# STM32WL_ADC.net
KiCad netlist of a schematic drawn in Altium Designer
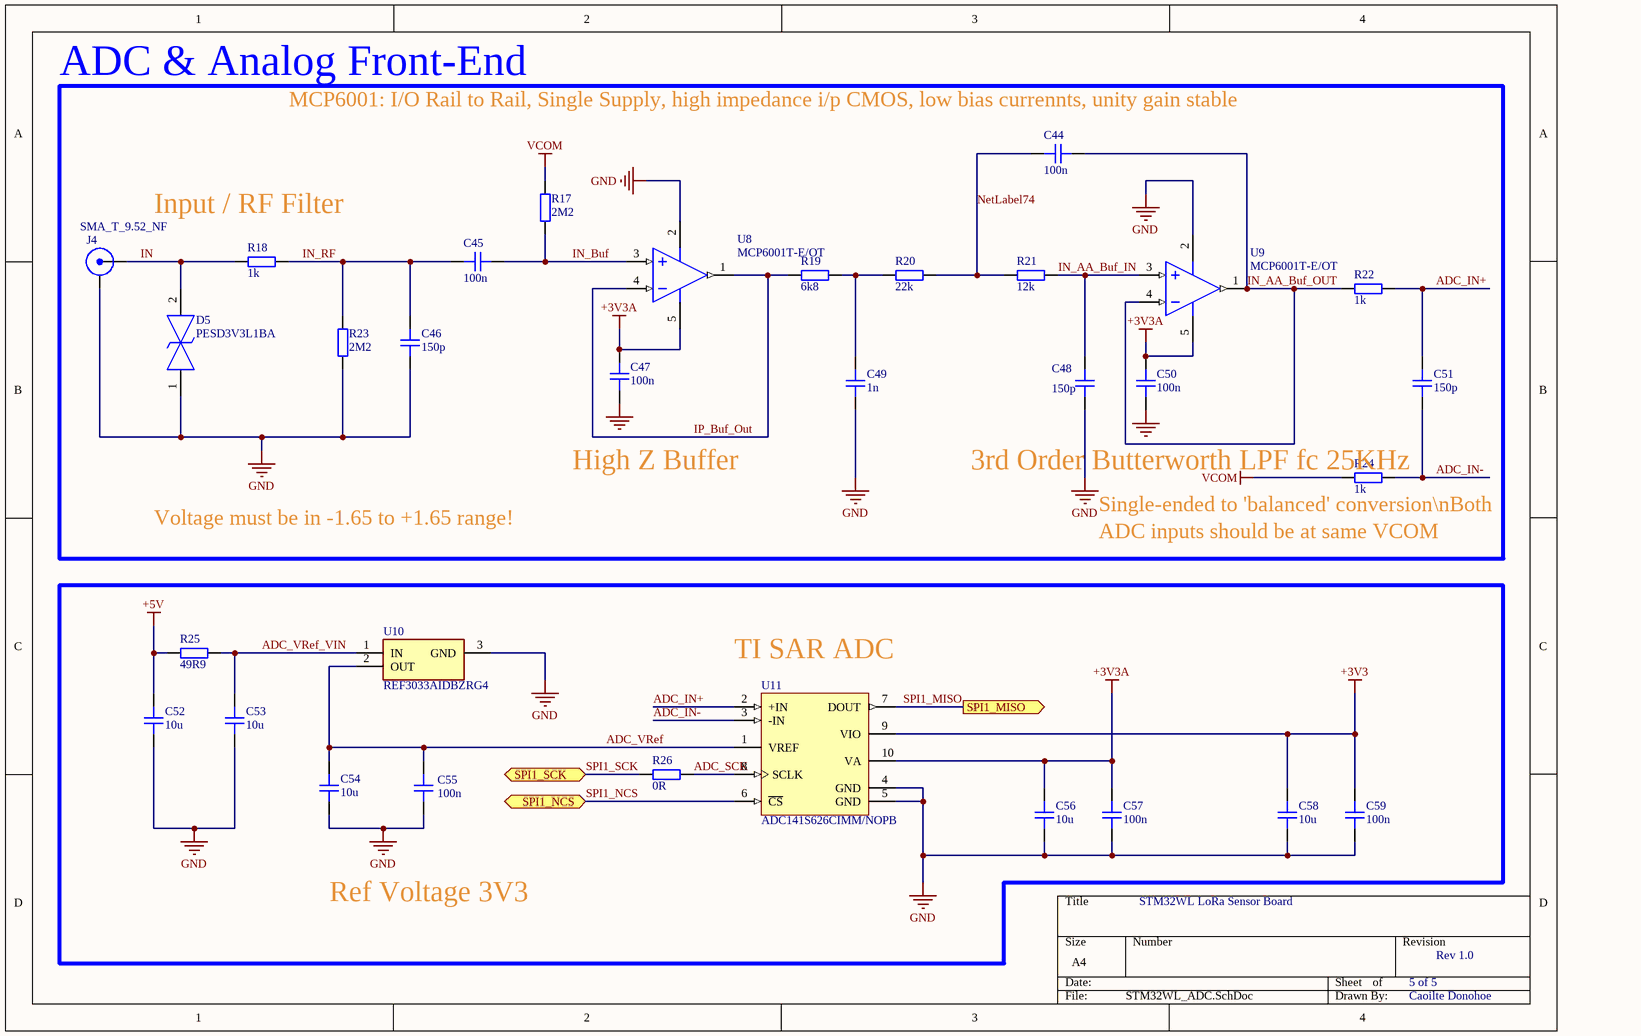
[diagram p0: STM32WL_ADC.SchDoc]

(export (version "E")
  (design (tool "Eeschema 10.0.6"))
  (components
    (comp (ref "C44")
      (value "100n")
      (footprint "CAP_0402")
      (description "Capacitor SMD 0402 16V")
      (libsource (lib "Schematic-Lib-PhilsLab") (part "CAP_0402_16V"))
    )
    (comp (ref "C45")
      (value "100n")
      (footprint "CAP_0402")
      (description "Capacitor SMD 0402 16V")
      (libsource (lib "Schematic-Lib-PhilsLab") (part "CAP_0402_16V"))
    )
    (comp (ref "C46")
      (value "150p")
      (footprint "CAP_0402")
      (description "Capacitor SMD 0402 16V")
      (libsource (lib "Schematic-Lib-PhilsLab") (part "CAP_0402_16V"))
    )
    (comp (ref "C47")
      (value "100n")
      (footprint "CAP_0402")
      (description "Capacitor SMD 0402 16V")
      (libsource (lib "Schematic-Lib-PhilsLab") (part "CAP_0402_16V"))
    )
    (comp (ref "C48")
      (value "150p")
      (footprint "CAP_0402")
      (description "Capacitor SMD 0402 16V")
      (libsource (lib "Schematic-Lib-PhilsLab") (part "CAP_0402_16V"))
    )
    (comp (ref "C49")
      (value "1n")
      (footprint "CAP_0402")
      (description "Capacitor SMD 0402 16V")
      (libsource (lib "Schematic-Lib-PhilsLab") (part "CAP_0402_16V"))
    )
    (comp (ref "C50")
      (value "100n")
      (footprint "CAP_0402")
      (description "Capacitor SMD 0402 16V")
      (libsource (lib "Schematic-Lib-PhilsLab") (part "CAP_0402_16V"))
    )
    (comp (ref "C51")
      (value "150p")
      (footprint "CAP_0402")
      (description "Capacitor SMD 0402 16V")
      (libsource (lib "Schematic-Lib-PhilsLab") (part "CAP_0402_16V"))
    )
    (comp (ref "C52")
      (value "10u")
      (footprint "CAP_0603")
      (description "Capacitor SMD 0603 16V")
      (libsource (lib "Schematic-Lib-PhilsLab") (part "CAP_0603_16V"))
    )
    (comp (ref "C53")
      (value "10u")
      (footprint "CAP_0603")
      (description "Capacitor SMD 0603 16V")
      (libsource (lib "Schematic-Lib-PhilsLab") (part "CAP_0603_16V"))
    )
    (comp (ref "C54")
      (value "10u")
      (footprint "CAP_0603")
      (description "Capacitor SMD 0603 16V")
      (libsource (lib "Schematic-Lib-PhilsLab") (part "CAP_0603_16V"))
    )
    (comp (ref "C55")
      (value "100n")
      (footprint "CAP_0402")
      (description "Capacitor SMD 0402 16V")
      (libsource (lib "Schematic-Lib-PhilsLab") (part "CAP_0402_16V"))
    )
    (comp (ref "C56")
      (value "10u")
      (footprint "CAP_0603")
      (description "Capacitor SMD 0603 16V")
      (libsource (lib "Schematic-Lib-PhilsLab") (part "CAP_0603_16V"))
    )
    (comp (ref "C57")
      (value "100n")
      (footprint "CAP_0402")
      (description "Capacitor SMD 0402 16V")
      (libsource (lib "Schematic-Lib-PhilsLab") (part "CAP_0402_16V"))
    )
    (comp (ref "C58")
      (value "10u")
      (footprint "CAP_0603")
      (description "Capacitor SMD 0603 16V")
      (libsource (lib "Schematic-Lib-PhilsLab") (part "CAP_0603_16V"))
    )
    (comp (ref "C59")
      (value "100n")
      (footprint "CAP_0402")
      (description "Capacitor SMD 0402 16V")
      (libsource (lib "Schematic-Lib-PhilsLab") (part "CAP_0402_16V"))
    )
    (comp (ref "D5")
      (value "PESD3V3L1BA")
      (footprint "SamacSys:SOD2512X110N")
      (description "TVS Diode (Bi-directional)")
      (libsource (lib "*") (part "PESD3V3L1BA"))
    )
    (comp (ref "J4")
      (value "SMA_T_9.52_NF")
      (footprint "CO_SAMTEC_SMA-J-P-ST-EMI")
      (description "SMA End Launch Jack 1.0 mm Board, 50 ohm")
      (fields
        (field (name "MANUFACTURER") "COAX CONNECTORS LTD")
        (field (name "MANUFACTURER_PART_NUMBER") "30-462-D3-1.1mm")
      )
      (libsource (lib "MB1789_HP") (part "SMA_T_9.52_NF"))
    )
    (comp (ref "R17")
      (value "2M2")
      (footprint "RES_0402")
      (description "Resistor SMD 0402")
      (libsource (lib "Schematic-Lib-PhilsLab") (part "RES_0402"))
    )
    (comp (ref "R18")
      (value "1k")
      (footprint "RES_0402")
      (description "Resistor SMD 0402")
      (libsource (lib "Schematic-Lib-PhilsLab") (part "RES_0402"))
    )
    (comp (ref "R19")
      (value "6k8")
      (footprint "RES_0402")
      (description "Resistor SMD 0402")
      (libsource (lib "Schematic-Lib-PhilsLab") (part "RES_0402"))
    )
    (comp (ref "R20")
      (value "22k")
      (footprint "RES_0402")
      (description "Resistor SMD 0402")
      (libsource (lib "Schematic-Lib-PhilsLab") (part "RES_0402"))
    )
    (comp (ref "R21")
      (value "12k")
      (footprint "RES_0402")
      (description "Resistor SMD 0402")
      (libsource (lib "Schematic-Lib-PhilsLab") (part "RES_0402"))
    )
    (comp (ref "R22")
      (value "1k")
      (footprint "RES_0402")
      (description "Resistor SMD 0402")
      (libsource (lib "Schematic-Lib-PhilsLab") (part "RES_0402"))
    )
    (comp (ref "R23")
      (value "2M2")
      (footprint "RES_0402")
      (description "Resistor SMD 0402")
      (libsource (lib "Schematic-Lib-PhilsLab") (part "RES_0402"))
    )
    (comp (ref "R24")
      (value "1k")
      (footprint "RES_0402")
      (description "Resistor SMD 0402")
      (libsource (lib "Schematic-Lib-PhilsLab") (part "RES_0402"))
    )
    (comp (ref "R25")
      (value "49R9")
      (footprint "RES_0402")
      (description "Resistor SMD 0402")
      (libsource (lib "Schematic-Lib-PhilsLab") (part "RES_0402"))
    )
    (comp (ref "R26")
      (value "0R")
      (footprint "RES_0402")
      (description "Resistor SMD 0402")
      (libsource (lib "Schematic-Lib-PhilsLab") (part "RES_0402"))
    )
    (comp (ref "U8")
      (value "MCP6001T-E/OT")
      (footprint "SOT-23-OT5_L")
      (description "None")
      (fields (field (name "VOLTAGE") "6V"))
      (libsource (lib "Altium Content Vault") (part "AMP-OPA-MCP6001-SOT5"))
    )
    (comp (ref "U9")
      (value "MCP6001T-E/OT")
      (footprint "SOT-23-OT5_L")
      (description "None")
      (fields (field (name "VOLTAGE") "6V"))
      (libsource (lib "Altium Content Vault") (part "AMP-OPA-MCP6001-SOT5"))
    )
    (comp (ref "U10")
      (value "REF3033AIDBZRG4")
      (footprint "SamacSys:SOT95P237X112-3N")
      (description "Integrated Circuit")
      (fields (field (name "MOUSER PART NUMBER") "595-REF3033AIDBZRG4"))
      (libsource (lib "*") (part "REF3033AIDBZRG4"))
    )
    (comp (ref "U11")
      (value "ADC141S626CIMM/NOPB")
      (footprint "MUB10A_M")
      (fields (field (name "MANUFACTURER") "National Semiconductor"))
      (libsource (lib "Altium Content Vault") (part "CON-ADC-ADC141S626CIMM"))
    )
  )
  (nets
    (net (code "1") (name "+3V3") (class "Default")
      (node (ref "C58") (pin "2") (pinfunction "2_2") (pintype "passive"))
      (node (ref "C59") (pin "2") (pinfunction "2_2") (pintype "passive"))
      (node (ref "U11") (pin "9") (pinfunction "VIO_9") (pintype "power_in"))
    )
    (net (code "2") (name "+3V3A") (class "Default")
      (node (ref "C47") (pin "1") (pinfunction "1_1") (pintype "passive"))
      (node (ref "C50") (pin "1") (pinfunction "1_1") (pintype "passive"))
      (node (ref "C56") (pin "2") (pinfunction "2_2") (pintype "passive"))
      (node (ref "C57") (pin "2") (pinfunction "2_2") (pintype "passive"))
      (node (ref "U11") (pin "10") (pinfunction "VA_10") (pintype "power_in"))
      (node (ref "U8") (pin "5") (pinfunction "VDD_5") (pintype "power_in"))
      (node (ref "U9") (pin "5") (pinfunction "VDD_5") (pintype "power_in"))
    )
    (net (code "3") (name "+5V") (class "Default")
      (node (ref "C52") (pin "2") (pinfunction "2_2") (pintype "passive"))
      (node (ref "R25") (pin "1") (pinfunction "1_1") (pintype "passive"))
    )
    (net (code "4") (name "/ADC_IN+") (class "Default")
      (node (ref "C51") (pin "1") (pinfunction "1_1") (pintype "passive"))
      (node (ref "R22") (pin "1") (pinfunction "1_1") (pintype "passive"))
      (node (ref "U11") (pin "2") (pinfunction "+IN_2") (pintype "input"))
    )
    (net (code "5") (name "/ADC_IN-") (class "Default")
      (node (ref "C51") (pin "2") (pinfunction "2_2") (pintype "passive"))
      (node (ref "R24") (pin "1") (pinfunction "1_1") (pintype "passive"))
      (node (ref "U11") (pin "3") (pinfunction "-IN_3") (pintype "input"))
    )
    (net (code "6") (name "/ADC_SCK") (class "Default")
      (node (ref "R26") (pin "2") (pinfunction "2_2") (pintype "passive"))
      (node (ref "U11") (pin "8") (pinfunction "SCLK_8") (pintype "input"))
    )
    (net (code "7") (name "/ADC_VRef") (class "Default")
      (node (ref "C54") (pin "2") (pinfunction "2_2") (pintype "passive"))
      (node (ref "C55") (pin "2") (pinfunction "2_2") (pintype "passive"))
      (node (ref "U10") (pin "2") (pinfunction "OUT_2") (pintype "passive"))
      (node (ref "U11") (pin "1") (pinfunction "VREF_1") (pintype "power_in"))
    )
    (net (code "8") (name "/ADC_VRef_VIN") (class "Default")
      (node (ref "C53") (pin "2") (pinfunction "2_2") (pintype "passive"))
      (node (ref "R25") (pin "2") (pinfunction "2_2") (pintype "passive"))
      (node (ref "U10") (pin "1") (pinfunction "IN_1") (pintype "passive"))
    )
    (net (code "9") (name "/IN") (class "Default")
      (node (ref "D5") (pin "2") (pinfunction "2_2") (pintype "passive"))
      (node (ref "J4") (pin "1") (pinfunction "X_1") (pintype "passive"))
      (node (ref "R18") (pin "1") (pinfunction "1_1") (pintype "passive"))
    )
    (net (code "10") (name "/IN_AA_Buf_IN") (class "Default")
      (node (ref "C48") (pin "2") (pinfunction "2_2") (pintype "passive"))
      (node (ref "R21") (pin "1") (pinfunction "1_1") (pintype "passive"))
      (node (ref "U9") (pin "3") (pinfunction "VIN+_3") (pintype "input"))
    )
    (net (code "11") (name "/IN_AA_Buf_OUT") (class "Default")
      (node (ref "C44") (pin "1") (pinfunction "1_1") (pintype "passive"))
      (node (ref "R22") (pin "2") (pinfunction "2_2") (pintype "passive"))
      (node (ref "U9") (pin "1") (pinfunction "VOUT_1") (pintype "output"))
      (node (ref "U9") (pin "4") (pinfunction "VIN-_4") (pintype "input"))
    )
    (net (code "12") (name "/IN_Buf") (class "Default")
      (node (ref "C45") (pin "1") (pinfunction "1_1") (pintype "passive"))
      (node (ref "R17") (pin "1") (pinfunction "1_1") (pintype "passive"))
      (node (ref "U8") (pin "3") (pinfunction "VIN+_3") (pintype "input"))
    )
    (net (code "13") (name "/IN_RF") (class "Default")
      (node (ref "C45") (pin "2") (pinfunction "2_2") (pintype "passive"))
      (node (ref "C46") (pin "2") (pinfunction "2_2") (pintype "passive"))
      (node (ref "R18") (pin "2") (pinfunction "2_2") (pintype "passive"))
      (node (ref "R23") (pin "2") (pinfunction "2_2") (pintype "passive"))
    )
    (net (code "14") (name "/IP_Buf_Out") (class "Default")
      (node (ref "R19") (pin "2") (pinfunction "2_2") (pintype "passive"))
      (node (ref "U8") (pin "1") (pinfunction "VOUT_1") (pintype "output"))
      (node (ref "U8") (pin "4") (pinfunction "VIN-_4") (pintype "input"))
    )
    (net (code "15") (name "/NetLabel74") (class "Default")
      (node (ref "C44") (pin "2") (pinfunction "2_2") (pintype "passive"))
      (node (ref "R20") (pin "1") (pinfunction "1_1") (pintype "passive"))
      (node (ref "R21") (pin "2") (pinfunction "2_2") (pintype "passive"))
    )
    (net (code "16") (name "/SPI1_MISO") (class "Default")
      (node (ref "U11") (pin "7") (pinfunction "DOUT_7") (pintype "output"))
    )
    (net (code "17") (name "/SPI1_NCS") (class "Default")
      (node (ref "U11") (pin "6") (pinfunction "~{CS}_6") (pintype "input"))
    )
    (net (code "18") (name "/SPI1_SCK") (class "Default")
      (node (ref "R26") (pin "1") (pinfunction "1_1") (pintype "passive"))
    )
    (net (code "19") (name "GND") (class "Default")
      (node (ref "C46") (pin "1") (pinfunction "1_1") (pintype "passive"))
      (node (ref "C47") (pin "2") (pinfunction "2_2") (pintype "passive"))
      (node (ref "C48") (pin "1") (pinfunction "1_1") (pintype "passive"))
      (node (ref "C49") (pin "1") (pinfunction "1_1") (pintype "passive"))
      (node (ref "C50") (pin "2") (pinfunction "2_2") (pintype "passive"))
      (node (ref "C52") (pin "1") (pinfunction "1_1") (pintype "passive"))
      (node (ref "C53") (pin "1") (pinfunction "1_1") (pintype "passive"))
      (node (ref "C54") (pin "1") (pinfunction "1_1") (pintype "passive"))
      (node (ref "C55") (pin "1") (pinfunction "1_1") (pintype "passive"))
      (node (ref "C56") (pin "1") (pinfunction "1_1") (pintype "passive"))
      (node (ref "C57") (pin "1") (pinfunction "1_1") (pintype "passive"))
      (node (ref "C58") (pin "1") (pinfunction "1_1") (pintype "passive"))
      (node (ref "C59") (pin "1") (pinfunction "1_1") (pintype "passive"))
      (node (ref "D5") (pin "1") (pinfunction "1_1") (pintype "passive"))
      (node (ref "J4") (pin "2") (pinfunction "Y_2") (pintype "passive"))
      (node (ref "R23") (pin "1") (pinfunction "1_1") (pintype "passive"))
      (node (ref "U10") (pin "3") (pinfunction "GND_3") (pintype "passive"))
      (node (ref "U11") (pin "4") (pinfunction "GND_4") (pintype "power_in"))
      (node (ref "U11") (pin "5") (pinfunction "GND_5") (pintype "power_in"))
      (node (ref "U8") (pin "2") (pinfunction "VSS_2") (pintype "power_in"))
      (node (ref "U9") (pin "2") (pinfunction "VSS_2") (pintype "power_in"))
    )
    (net (code "20") (name "Net-(C49-Pad2)") (class "Default")
      (node (ref "C49") (pin "2") (pinfunction "2_2") (pintype "passive"))
      (node (ref "R19") (pin "1") (pinfunction "1_1") (pintype "passive"))
      (node (ref "R20") (pin "2") (pinfunction "2_2") (pintype "passive"))
    )
    (net (code "21") (name "VCOM") (class "Default")
      (node (ref "R17") (pin "2") (pinfunction "2_2") (pintype "passive"))
      (node (ref "R24") (pin "2") (pinfunction "2_2") (pintype "passive"))
    )
  )
)
